# MasterOpAmp-design.net
KiCad netlist of a schematic drawn in EAGLE
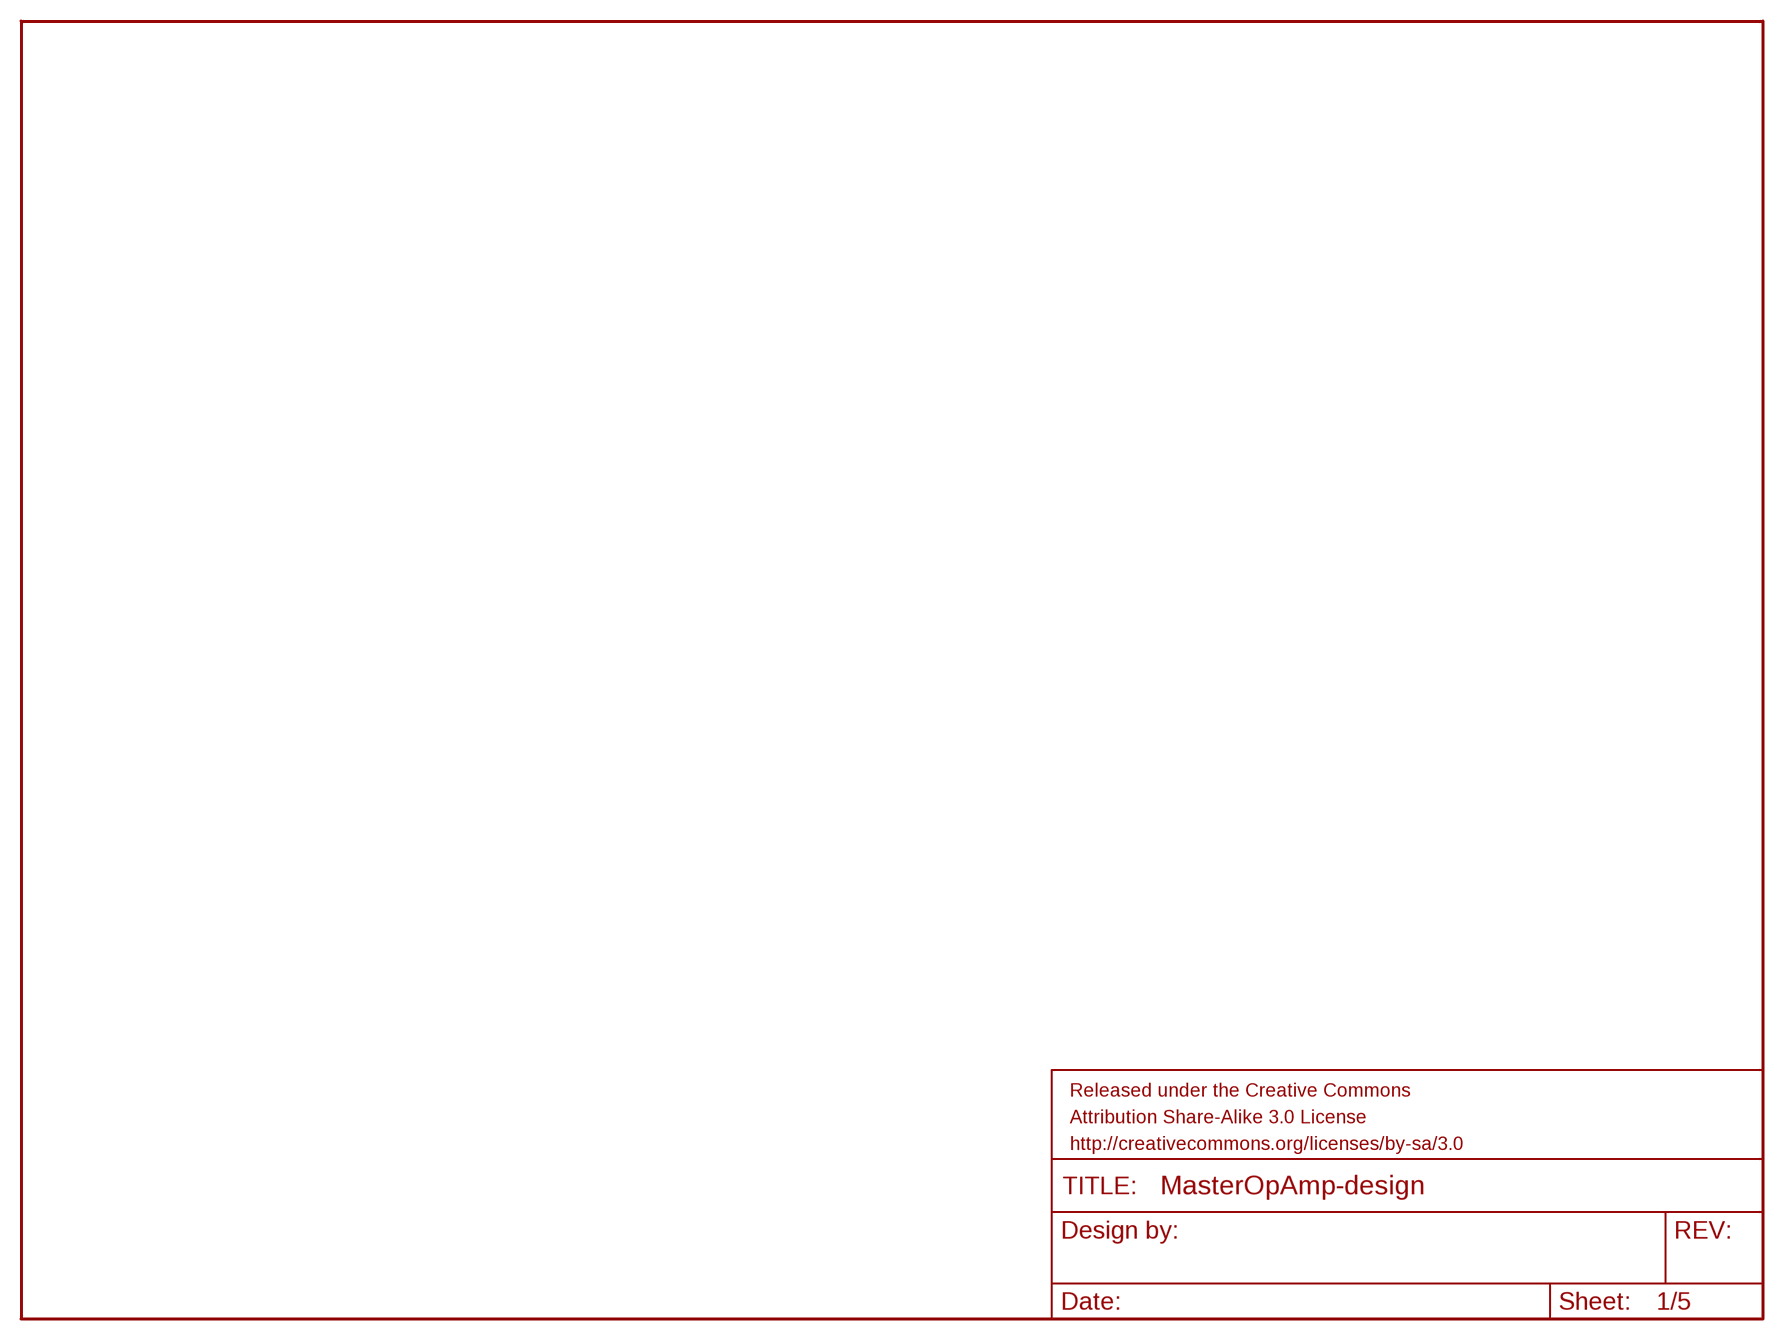
[diagram p0: schematic, sheet 1]
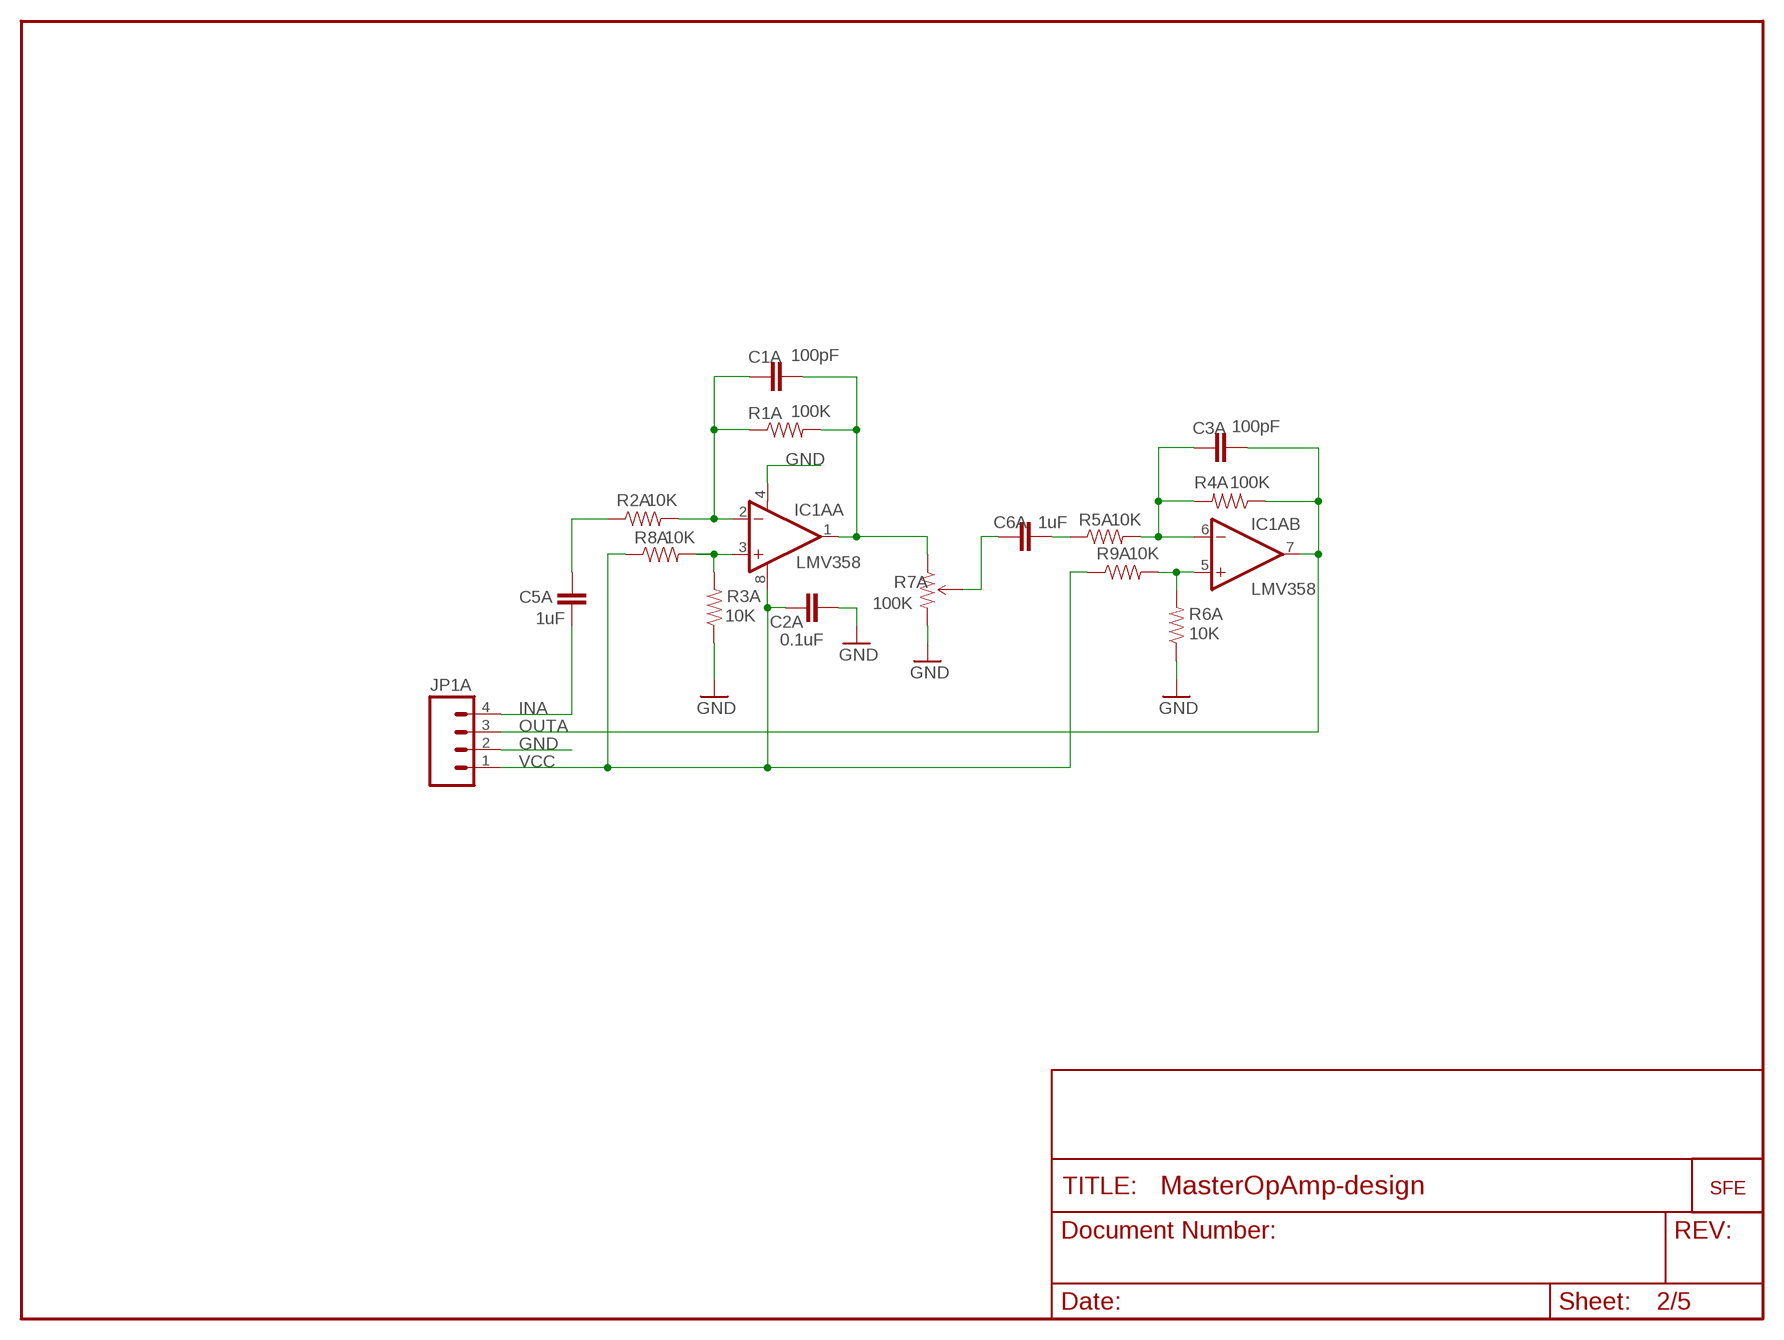
[diagram p1: schematic, sheet 2]
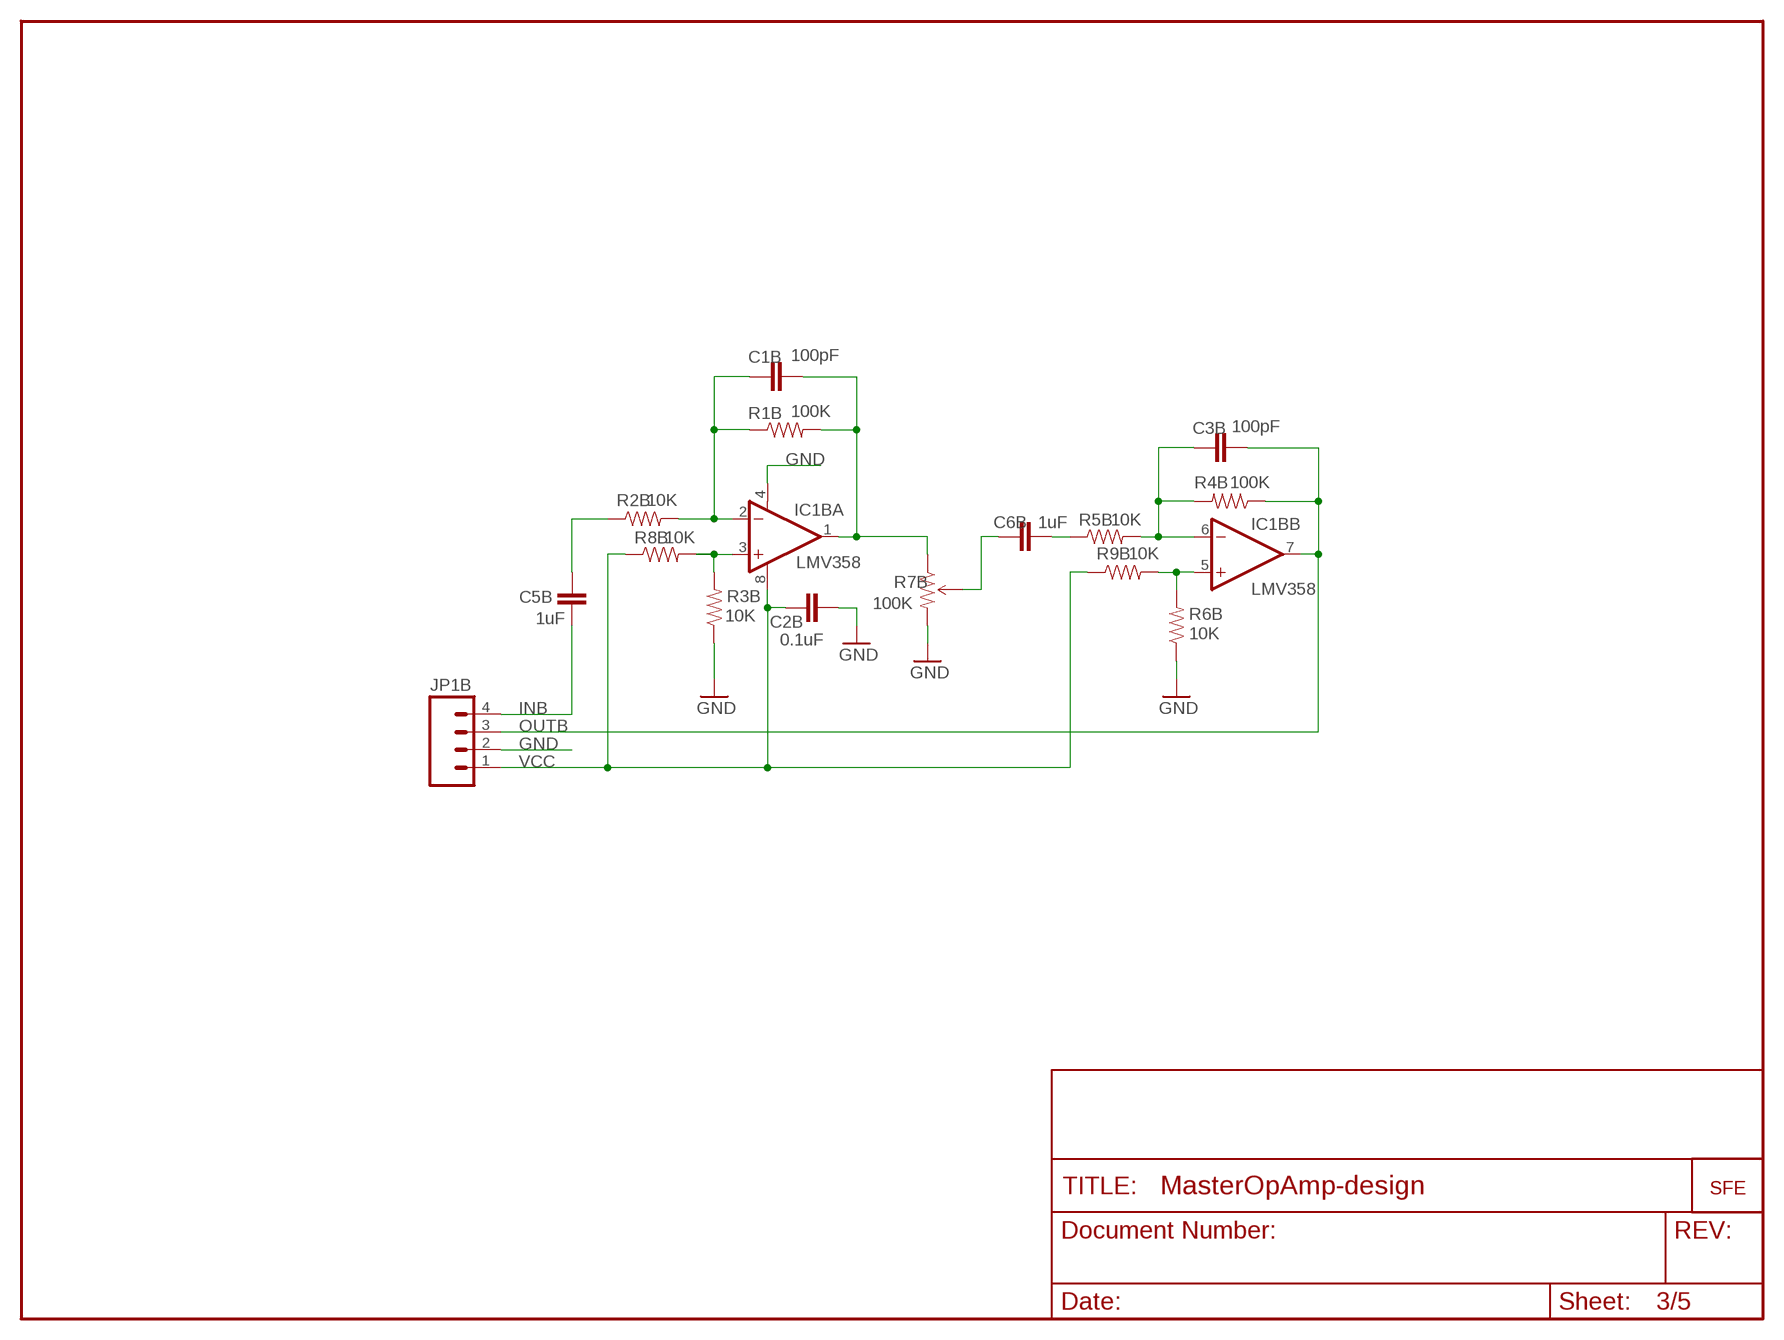
[diagram p2: schematic, sheet 3]
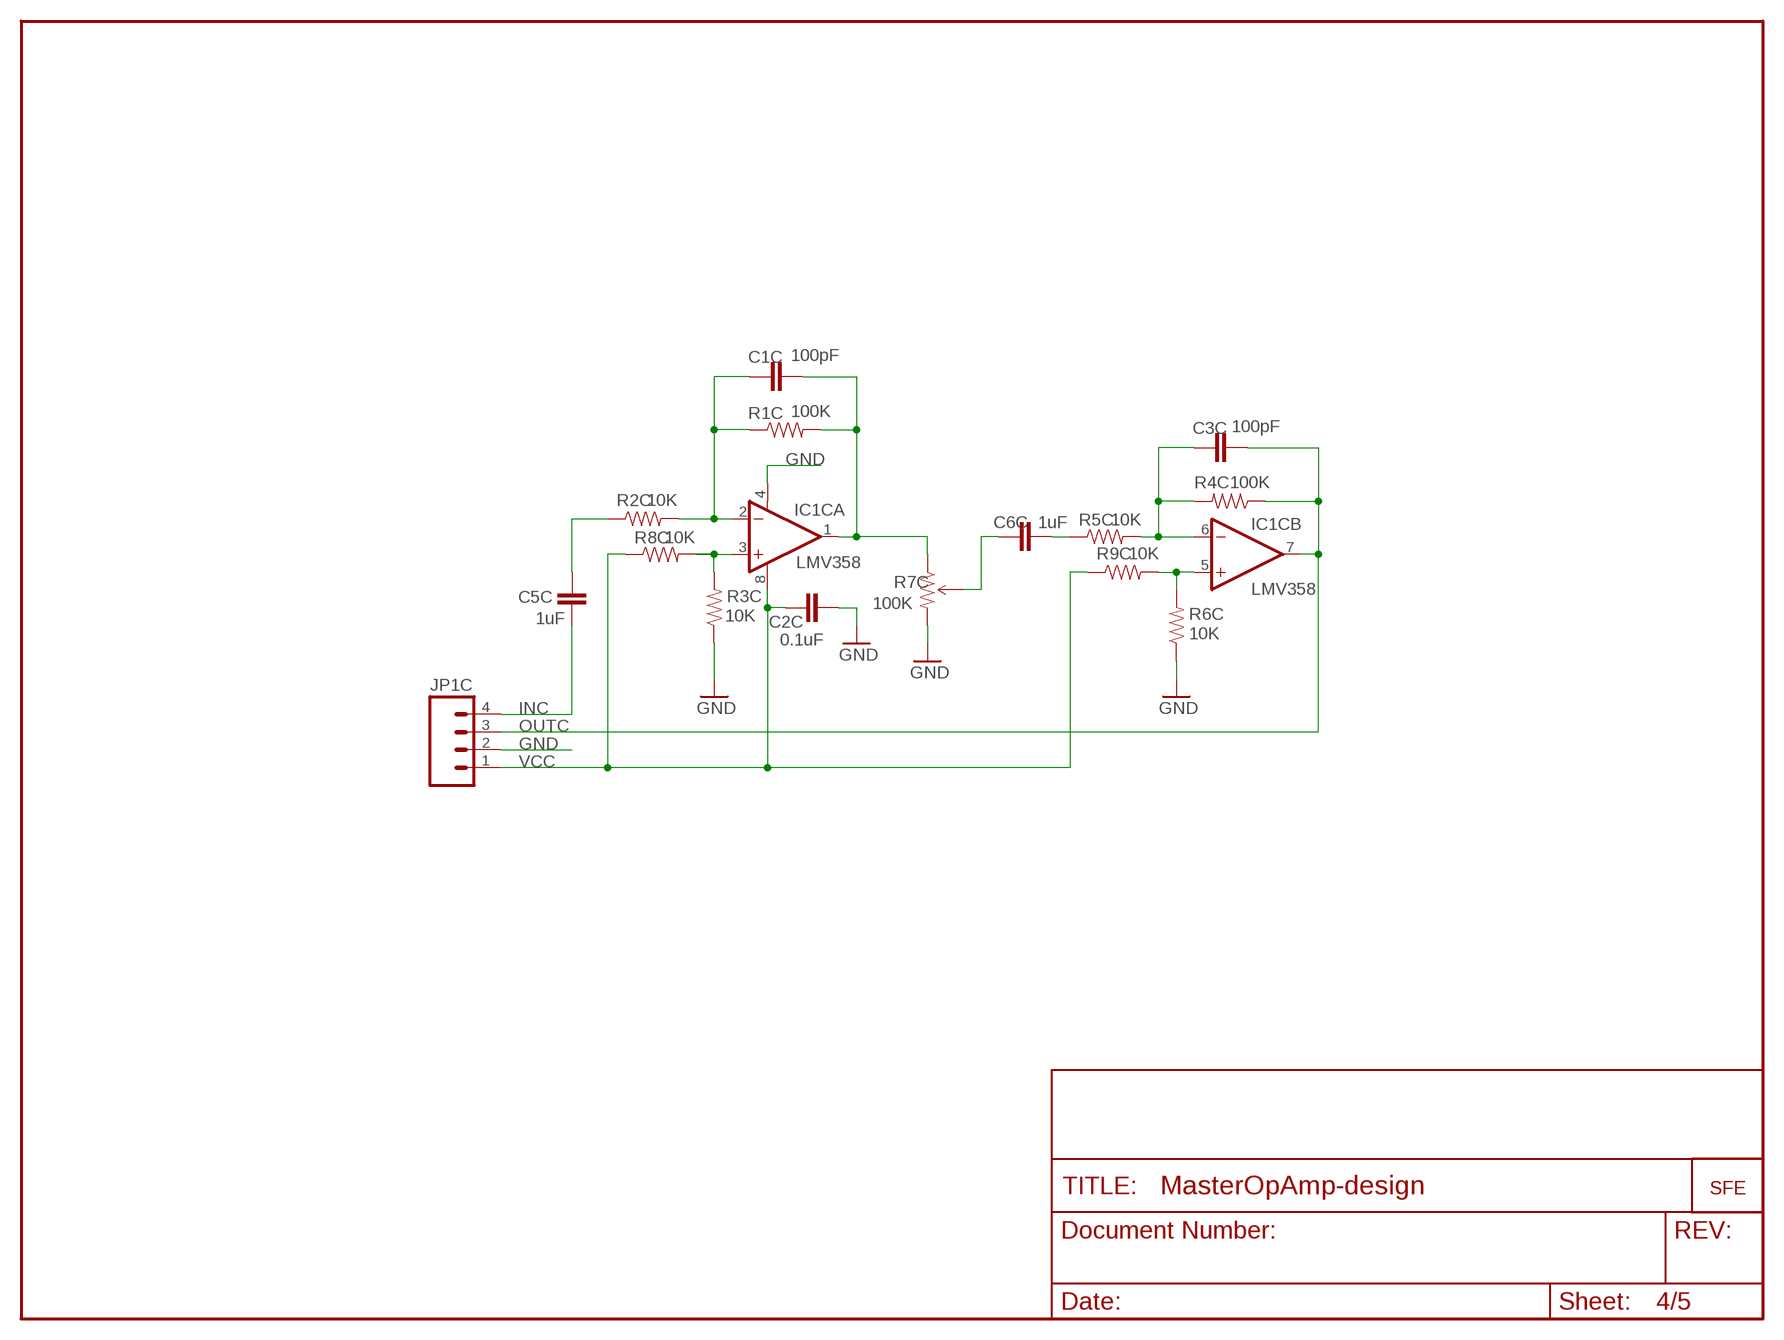
[diagram p3: schematic, sheet 4]
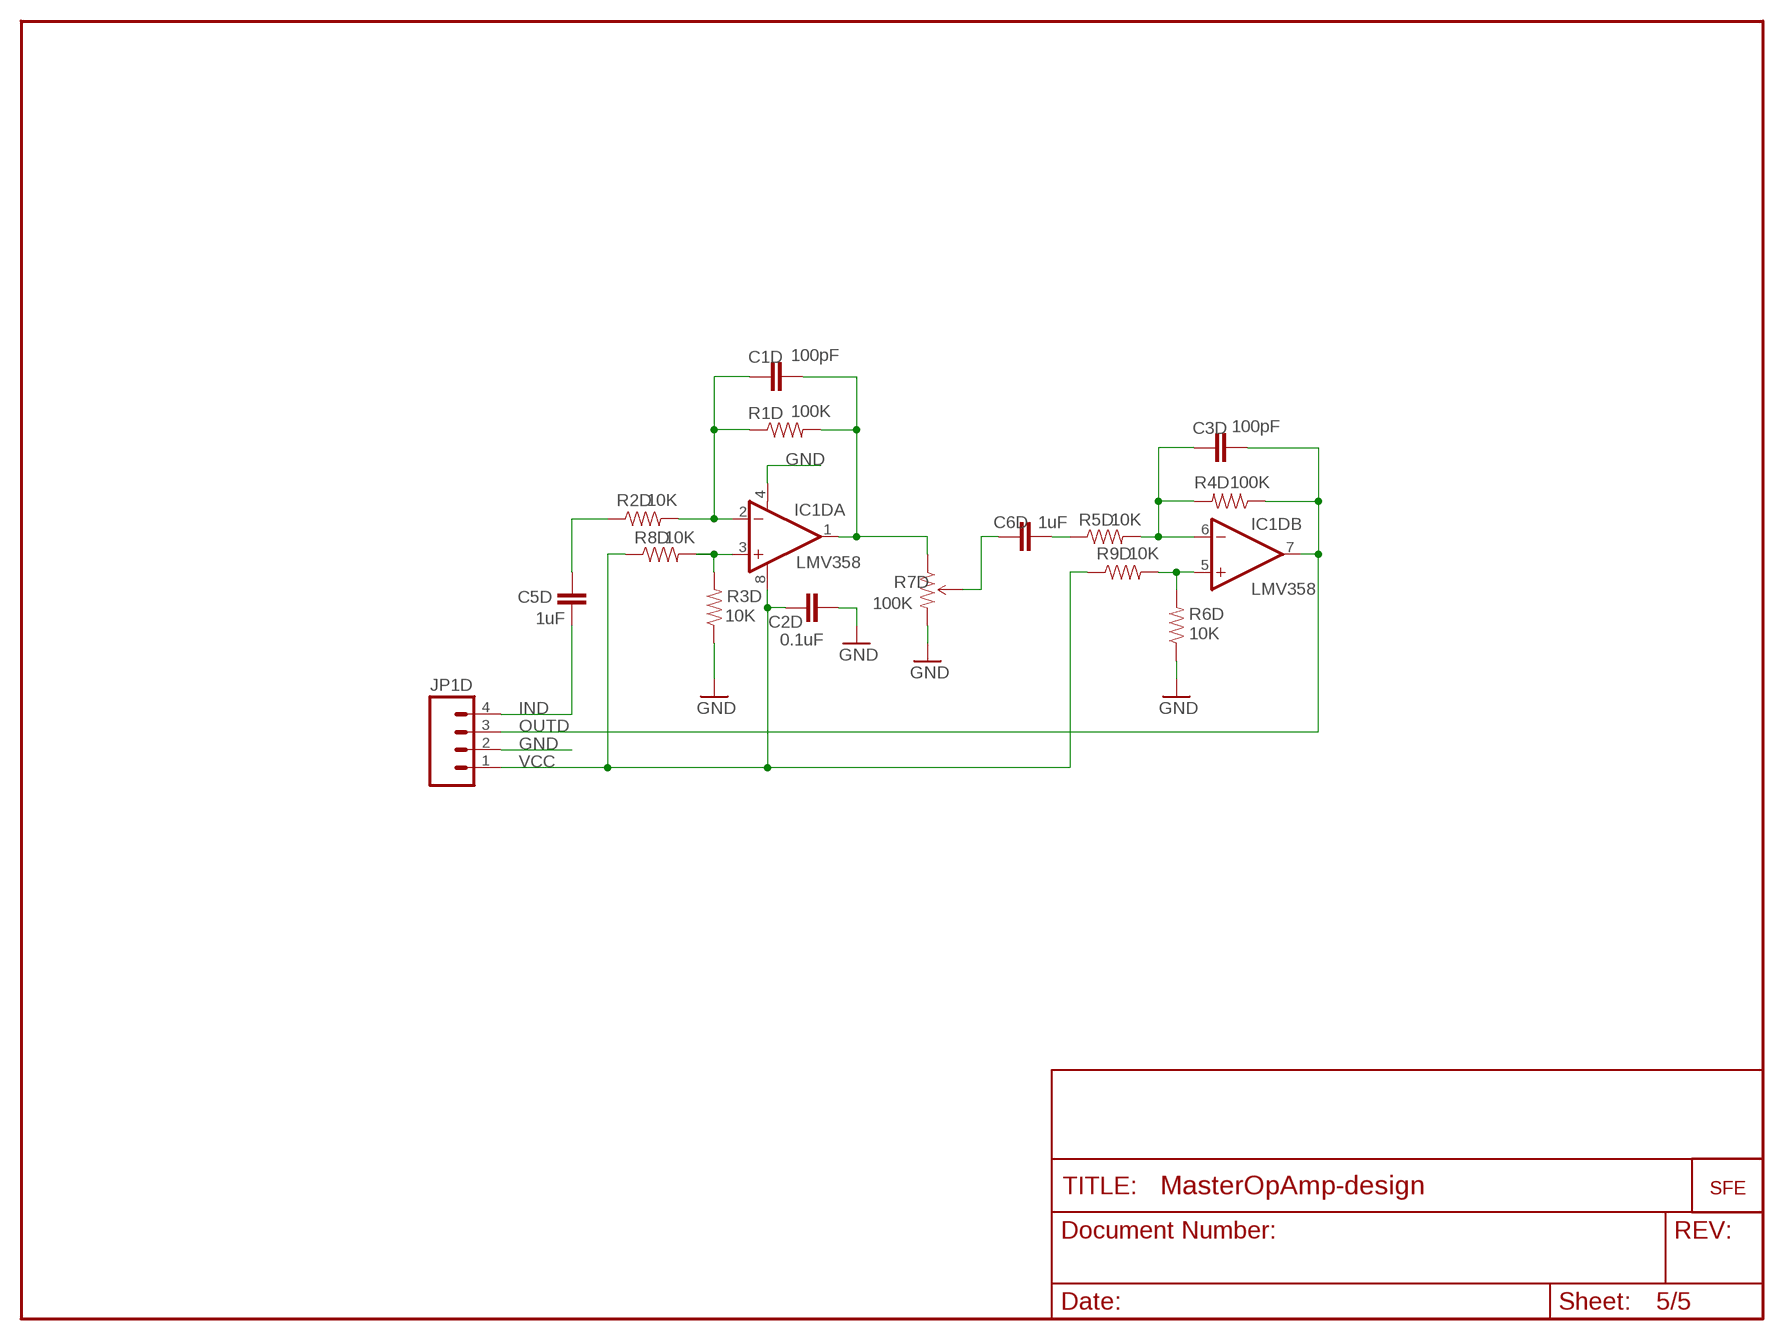
[diagram p4: schematic, sheet 5]

(export (version "E")
  (design (tool "Eeschema 10.0.6"))
  (components
    (comp (ref "C1A")
      (value "100pF")
      (footprint "eagle-import:C0402")
      (libsource (lib "eagle-import") (part "CAP0402"))
    )
    (comp (ref "C2A")
      (value "0.1uF")
      (footprint "eagle-import:C0402")
      (libsource (lib "eagle-import") (part "CAP0402"))
    )
    (comp (ref "C3A")
      (value "100pF")
      (footprint "eagle-import:C0402")
      (libsource (lib "eagle-import") (part "CAP0402"))
    )
    (comp (ref "C5A")
      (value "1uF")
      (footprint "eagle-import:C0402")
      (libsource (lib "eagle-import") (part "CAP0402"))
    )
    (comp (ref "C6A")
      (value "1uF")
      (footprint "eagle-import:C0402")
      (libsource (lib "eagle-import") (part "CAP0402"))
    )
    (comp (ref "IC1A")
      (value "LMV358")
      (footprint "eagle-import:SO08")
      (libsource (lib "eagle-import") (part "OPAMP-DUALU"))
    )
    (comp (ref "JP1A")
      (value "M04PTH")
      (footprint "eagle-import:1X04")
      (libsource (lib "eagle-import") (part "M04PTH"))
    )
    (comp (ref "R1A")
      (value "100K")
      (footprint "eagle-import:C0402")
      (libsource (lib "eagle-import") (part "RESISTOR0402"))
    )
    (comp (ref "R2A")
      (value "10K")
      (footprint "eagle-import:C0402")
      (libsource (lib "eagle-import") (part "RESISTOR0402"))
    )
    (comp (ref "R3A")
      (value "10K")
      (footprint "eagle-import:C0402")
      (libsource (lib "eagle-import") (part "RESISTOR0402"))
    )
    (comp (ref "R4A")
      (value "100K")
      (footprint "eagle-import:C0402")
      (libsource (lib "eagle-import") (part "RESISTOR0402"))
    )
    (comp (ref "R5A")
      (value "10K")
      (footprint "eagle-import:C0402")
      (libsource (lib "eagle-import") (part "RESISTOR0402"))
    )
    (comp (ref "R6A")
      (value "10K")
      (footprint "eagle-import:C0402")
      (libsource (lib "eagle-import") (part "RESISTOR0402"))
    )
    (comp (ref "R7A")
      (value "100K")
      (footprint "eagle-import:TRIMPOT-3MM")
      (libsource (lib "eagle-import") (part "TRIMPOTSMD"))
    )
    (comp (ref "R8A")
      (value "10K")
      (footprint "eagle-import:C0402")
      (libsource (lib "eagle-import") (part "SparkFun-DC_RESISTOR0402"))
    )
    (comp (ref "R9A")
      (value "10K")
      (footprint "eagle-import:C0402")
      (libsource (lib "eagle-import") (part "SparkFun-DC_RESISTOR0402"))
    )
    (comp (ref "U$3A")
      (value "LOGO-SFENEW")
      (footprint "eagle-import:SFE-NEW-WEBLOGO")
      (libsource (lib "eagle-import") (part "LOGO-SFENEW"))
    )
    (comp (ref "FRAME1")
      (value "FRAME-LETTER")
      (footprint "eagle-import:CREATIVE_COMMONS")
      (libsource (lib "eagle-import") (part "SparkFun-Aesthetics_FRAME-LETTER"))
    )
    (comp (ref "C1B")
      (value "100pF")
      (footprint "eagle-import:C0402")
      (libsource (lib "eagle-import") (part "CAP0402"))
    )
    (comp (ref "C2B")
      (value "0.1uF")
      (footprint "eagle-import:C0402")
      (libsource (lib "eagle-import") (part "CAP0402"))
    )
    (comp (ref "C3B")
      (value "100pF")
      (footprint "eagle-import:C0402")
      (libsource (lib "eagle-import") (part "CAP0402"))
    )
    (comp (ref "C5B")
      (value "1uF")
      (footprint "eagle-import:C0402")
      (libsource (lib "eagle-import") (part "CAP0402"))
    )
    (comp (ref "C6B")
      (value "1uF")
      (footprint "eagle-import:C0402")
      (libsource (lib "eagle-import") (part "CAP0402"))
    )
    (comp (ref "IC1B")
      (value "LMV358")
      (footprint "eagle-import:SO08")
      (libsource (lib "eagle-import") (part "OPAMP-DUALU"))
    )
    (comp (ref "JP1B")
      (value "M04PTH")
      (footprint "eagle-import:1X04")
      (libsource (lib "eagle-import") (part "M04PTH"))
    )
    (comp (ref "R1B")
      (value "100K")
      (footprint "eagle-import:C0402")
      (libsource (lib "eagle-import") (part "RESISTOR0402"))
    )
    (comp (ref "R2B")
      (value "10K")
      (footprint "eagle-import:C0402")
      (libsource (lib "eagle-import") (part "RESISTOR0402"))
    )
    (comp (ref "R3B")
      (value "10K")
      (footprint "eagle-import:C0402")
      (libsource (lib "eagle-import") (part "RESISTOR0402"))
    )
    (comp (ref "R4B")
      (value "100K")
      (footprint "eagle-import:C0402")
      (libsource (lib "eagle-import") (part "RESISTOR0402"))
    )
    (comp (ref "R5B")
      (value "10K")
      (footprint "eagle-import:C0402")
      (libsource (lib "eagle-import") (part "RESISTOR0402"))
    )
    (comp (ref "R6B")
      (value "10K")
      (footprint "eagle-import:C0402")
      (libsource (lib "eagle-import") (part "RESISTOR0402"))
    )
    (comp (ref "R7B")
      (value "100K")
      (footprint "eagle-import:TRIMPOT-3MM")
      (libsource (lib "eagle-import") (part "TRIMPOTSMD"))
    )
    (comp (ref "R8B")
      (value "10K")
      (footprint "eagle-import:C0402")
      (libsource (lib "eagle-import") (part "SparkFun-DC_RESISTOR0402"))
    )
    (comp (ref "R9B")
      (value "10K")
      (footprint "eagle-import:C0402")
      (libsource (lib "eagle-import") (part "SparkFun-DC_RESISTOR0402"))
    )
    (comp (ref "U$3B")
      (value "LOGO-SFENEW")
      (footprint "eagle-import:SFE-NEW-WEBLOGO")
      (libsource (lib "eagle-import") (part "LOGO-SFENEW"))
    )
    (comp (ref "C1C")
      (value "100pF")
      (footprint "eagle-import:C0402")
      (libsource (lib "eagle-import") (part "CAP0402"))
    )
    (comp (ref "C2C")
      (value "0.1uF")
      (footprint "eagle-import:C0402")
      (libsource (lib "eagle-import") (part "CAP0402"))
    )
    (comp (ref "C3C")
      (value "100pF")
      (footprint "eagle-import:C0402")
      (libsource (lib "eagle-import") (part "CAP0402"))
    )
    (comp (ref "C5C")
      (value "1uF")
      (footprint "eagle-import:C0402")
      (libsource (lib "eagle-import") (part "CAP0402"))
    )
    (comp (ref "C6C")
      (value "1uF")
      (footprint "eagle-import:C0402")
      (libsource (lib "eagle-import") (part "CAP0402"))
    )
    (comp (ref "IC1C")
      (value "LMV358")
      (footprint "eagle-import:SO08")
      (libsource (lib "eagle-import") (part "OPAMP-DUALU"))
    )
    (comp (ref "JP1C")
      (value "M04PTH")
      (footprint "eagle-import:1X04")
      (libsource (lib "eagle-import") (part "M04PTH"))
    )
    (comp (ref "R1C")
      (value "100K")
      (footprint "eagle-import:C0402")
      (libsource (lib "eagle-import") (part "RESISTOR0402"))
    )
    (comp (ref "R2C")
      (value "10K")
      (footprint "eagle-import:C0402")
      (libsource (lib "eagle-import") (part "RESISTOR0402"))
    )
    (comp (ref "R3C")
      (value "10K")
      (footprint "eagle-import:C0402")
      (libsource (lib "eagle-import") (part "RESISTOR0402"))
    )
    (comp (ref "R4C")
      (value "100K")
      (footprint "eagle-import:C0402")
      (libsource (lib "eagle-import") (part "RESISTOR0402"))
    )
    (comp (ref "R5C")
      (value "10K")
      (footprint "eagle-import:C0402")
      (libsource (lib "eagle-import") (part "RESISTOR0402"))
    )
    (comp (ref "R6C")
      (value "10K")
      (footprint "eagle-import:C0402")
      (libsource (lib "eagle-import") (part "RESISTOR0402"))
    )
    (comp (ref "R7C")
      (value "100K")
      (footprint "eagle-import:TRIMPOT-3MM")
      (libsource (lib "eagle-import") (part "TRIMPOTSMD"))
    )
    (comp (ref "R8C")
      (value "10K")
      (footprint "eagle-import:C0402")
      (libsource (lib "eagle-import") (part "SparkFun-DC_RESISTOR0402"))
    )
    (comp (ref "R9C")
      (value "10K")
      (footprint "eagle-import:C0402")
      (libsource (lib "eagle-import") (part "SparkFun-DC_RESISTOR0402"))
    )
    (comp (ref "U$3C")
      (value "LOGO-SFENEW")
      (footprint "eagle-import:SFE-NEW-WEBLOGO")
      (libsource (lib "eagle-import") (part "LOGO-SFENEW"))
    )
    (comp (ref "C1D")
      (value "100pF")
      (footprint "eagle-import:C0402")
      (libsource (lib "eagle-import") (part "CAP0402"))
    )
    (comp (ref "C2D")
      (value "0.1uF")
      (footprint "eagle-import:C0402")
      (libsource (lib "eagle-import") (part "CAP0402"))
    )
    (comp (ref "C3D")
      (value "100pF")
      (footprint "eagle-import:C0402")
      (libsource (lib "eagle-import") (part "CAP0402"))
    )
    (comp (ref "C5D")
      (value "1uF")
      (footprint "eagle-import:C0402")
      (libsource (lib "eagle-import") (part "CAP0402"))
    )
    (comp (ref "C6D")
      (value "1uF")
      (footprint "eagle-import:C0402")
      (libsource (lib "eagle-import") (part "CAP0402"))
    )
    (comp (ref "IC1D")
      (value "LMV358")
      (footprint "eagle-import:SO08")
      (libsource (lib "eagle-import") (part "OPAMP-DUALU"))
    )
    (comp (ref "JP1D")
      (value "M04PTH")
      (footprint "eagle-import:1X04")
      (libsource (lib "eagle-import") (part "M04PTH"))
    )
    (comp (ref "R1D")
      (value "100K")
      (footprint "eagle-import:C0402")
      (libsource (lib "eagle-import") (part "RESISTOR0402"))
    )
    (comp (ref "R2D")
      (value "10K")
      (footprint "eagle-import:C0402")
      (libsource (lib "eagle-import") (part "RESISTOR0402"))
    )
    (comp (ref "R3D")
      (value "10K")
      (footprint "eagle-import:C0402")
      (libsource (lib "eagle-import") (part "RESISTOR0402"))
    )
    (comp (ref "R4D")
      (value "100K")
      (footprint "eagle-import:C0402")
      (libsource (lib "eagle-import") (part "RESISTOR0402"))
    )
    (comp (ref "R5D")
      (value "10K")
      (footprint "eagle-import:C0402")
      (libsource (lib "eagle-import") (part "RESISTOR0402"))
    )
    (comp (ref "R6D")
      (value "10K")
      (footprint "eagle-import:C0402")
      (libsource (lib "eagle-import") (part "RESISTOR0402"))
    )
    (comp (ref "R7D")
      (value "100K")
      (footprint "eagle-import:TRIMPOT-3MM")
      (libsource (lib "eagle-import") (part "TRIMPOTSMD"))
    )
    (comp (ref "R8D")
      (value "10K")
      (footprint "eagle-import:C0402")
      (libsource (lib "eagle-import") (part "SparkFun-DC_RESISTOR0402"))
    )
    (comp (ref "R9D")
      (value "10K")
      (footprint "eagle-import:C0402")
      (libsource (lib "eagle-import") (part "SparkFun-DC_RESISTOR0402"))
    )
    (comp (ref "U$3D")
      (value "LOGO-SFENEW")
      (footprint "eagle-import:SFE-NEW-WEBLOGO")
      (libsource (lib "eagle-import") (part "LOGO-SFENEW"))
    )
  )
  (nets
    (net (code "1") (name "GND") (class "Default")
      (node (ref "C2A") (pin "2") (pinfunction "2_2") (pintype "passive"))
      (node (ref "C2B") (pin "2") (pinfunction "2_2") (pintype "passive"))
      (node (ref "C2C") (pin "2") (pinfunction "2_2") (pintype "passive"))
      (node (ref "C2D") (pin "2") (pinfunction "2_2") (pintype "passive"))
      (node (ref "IC1A") (pin "4") (pinfunction "V-_4") (pintype "power_in"))
      (node (ref "IC1B") (pin "4") (pinfunction "V-_4") (pintype "power_in"))
      (node (ref "IC1C") (pin "4") (pinfunction "V-_4") (pintype "power_in"))
      (node (ref "IC1D") (pin "4") (pinfunction "V-_4") (pintype "power_in"))
      (node (ref "JP1A") (pin "2") (pinfunction "2_2") (pintype "passive"))
      (node (ref "JP1B") (pin "2") (pinfunction "2_2") (pintype "passive"))
      (node (ref "JP1C") (pin "2") (pinfunction "2_2") (pintype "passive"))
      (node (ref "JP1D") (pin "2") (pinfunction "2_2") (pintype "passive"))
      (node (ref "R3A") (pin "1") (pinfunction "1_1") (pintype "passive"))
      (node (ref "R3B") (pin "1") (pinfunction "1_1") (pintype "passive"))
      (node (ref "R3C") (pin "1") (pinfunction "1_1") (pintype "passive"))
      (node (ref "R3D") (pin "1") (pinfunction "1_1") (pintype "passive"))
      (node (ref "R6A") (pin "1") (pinfunction "1_1") (pintype "passive"))
      (node (ref "R6B") (pin "1") (pinfunction "1_1") (pintype "passive"))
      (node (ref "R6C") (pin "1") (pinfunction "1_1") (pintype "passive"))
      (node (ref "R6D") (pin "1") (pinfunction "1_1") (pintype "passive"))
      (node (ref "R7A") (pin "3") (pinfunction "CW_3") (pintype "passive"))
      (node (ref "R7B") (pin "3") (pinfunction "CW_3") (pintype "passive"))
      (node (ref "R7C") (pin "3") (pinfunction "CW_3") (pintype "passive"))
      (node (ref "R7D") (pin "3") (pinfunction "CW_3") (pintype "passive"))
    )
    (net (code "2") (name "INA") (class "Default")
      (node (ref "C5A") (pin "1") (pinfunction "1_1") (pintype "passive"))
      (node (ref "JP1A") (pin "4") (pinfunction "4_4") (pintype "passive"))
    )
    (net (code "3") (name "INB") (class "Default")
      (node (ref "C5B") (pin "1") (pinfunction "1_1") (pintype "passive"))
      (node (ref "JP1B") (pin "4") (pinfunction "4_4") (pintype "passive"))
    )
    (net (code "4") (name "INC") (class "Default")
      (node (ref "C5C") (pin "1") (pinfunction "1_1") (pintype "passive"))
      (node (ref "JP1C") (pin "4") (pinfunction "4_4") (pintype "passive"))
    )
    (net (code "5") (name "IND") (class "Default")
      (node (ref "C5D") (pin "1") (pinfunction "1_1") (pintype "passive"))
      (node (ref "JP1D") (pin "4") (pinfunction "4_4") (pintype "passive"))
    )
    (net (code "6") (name "Net-(C5A-Pad2)") (class "Default")
      (node (ref "C5A") (pin "2") (pinfunction "2_2") (pintype "passive"))
      (node (ref "R2A") (pin "1") (pinfunction "1_1") (pintype "passive"))
    )
    (net (code "7") (name "Net-(C5B-Pad2)") (class "Default")
      (node (ref "C5B") (pin "2") (pinfunction "2_2") (pintype "passive"))
      (node (ref "R2B") (pin "1") (pinfunction "1_1") (pintype "passive"))
    )
    (net (code "8") (name "Net-(C5C-Pad2)") (class "Default")
      (node (ref "C5C") (pin "2") (pinfunction "2_2") (pintype "passive"))
      (node (ref "R2C") (pin "1") (pinfunction "1_1") (pintype "passive"))
    )
    (net (code "9") (name "Net-(C5D-Pad2)") (class "Default")
      (node (ref "C5D") (pin "2") (pinfunction "2_2") (pintype "passive"))
      (node (ref "R2D") (pin "1") (pinfunction "1_1") (pintype "passive"))
    )
    (net (code "10") (name "Net-(C6A-Pad1)") (class "Default")
      (node (ref "C6A") (pin "1") (pinfunction "1_1") (pintype "passive"))
      (node (ref "R5A") (pin "1") (pinfunction "1_1") (pintype "passive"))
    )
    (net (code "11") (name "Net-(C6B-Pad1)") (class "Default")
      (node (ref "C6B") (pin "1") (pinfunction "1_1") (pintype "passive"))
      (node (ref "R5B") (pin "1") (pinfunction "1_1") (pintype "passive"))
    )
    (net (code "12") (name "Net-(C6C-Pad1)") (class "Default")
      (node (ref "C6C") (pin "1") (pinfunction "1_1") (pintype "passive"))
      (node (ref "R5C") (pin "1") (pinfunction "1_1") (pintype "passive"))
    )
    (net (code "13") (name "Net-(C6D-Pad1)") (class "Default")
      (node (ref "C6D") (pin "1") (pinfunction "1_1") (pintype "passive"))
      (node (ref "R5D") (pin "1") (pinfunction "1_1") (pintype "passive"))
    )
    (net (code "14") (name "Net-(IC1AA-+IN)") (class "Default")
      (node (ref "IC1A") (pin "3") (pinfunction "+IN_3") (pintype "input"))
      (node (ref "R3A") (pin "2") (pinfunction "2_2") (pintype "passive"))
      (node (ref "R8A") (pin "2") (pinfunction "2_2") (pintype "passive"))
    )
    (net (code "15") (name "Net-(IC1AA--IN)") (class "Default")
      (node (ref "C1A") (pin "1") (pinfunction "1_1") (pintype "passive"))
      (node (ref "IC1A") (pin "2") (pinfunction "-IN_2") (pintype "input"))
      (node (ref "R1A") (pin "1") (pinfunction "1_1") (pintype "passive"))
      (node (ref "R2A") (pin "2") (pinfunction "2_2") (pintype "passive"))
    )
    (net (code "16") (name "Net-(IC1AA-OUT)") (class "Default")
      (node (ref "C1A") (pin "2") (pinfunction "2_2") (pintype "passive"))
      (node (ref "IC1A") (pin "1") (pinfunction "OUT_1") (pintype "output"))
      (node (ref "R1A") (pin "2") (pinfunction "2_2") (pintype "passive"))
      (node (ref "R7A") (pin "1") (pinfunction "CCW_1") (pintype "passive"))
    )
    (net (code "17") (name "Net-(IC1AB-+IN)") (class "Default")
      (node (ref "IC1A") (pin "5") (pinfunction "+IN_5") (pintype "input"))
      (node (ref "R6A") (pin "2") (pinfunction "2_2") (pintype "passive"))
      (node (ref "R9A") (pin "2") (pinfunction "2_2") (pintype "passive"))
    )
    (net (code "18") (name "Net-(IC1AB--IN)") (class "Default")
      (node (ref "C3A") (pin "1") (pinfunction "1_1") (pintype "passive"))
      (node (ref "IC1A") (pin "6") (pinfunction "-IN_6") (pintype "input"))
      (node (ref "R4A") (pin "2") (pinfunction "2_2") (pintype "passive"))
      (node (ref "R5A") (pin "2") (pinfunction "2_2") (pintype "passive"))
    )
    (net (code "19") (name "Net-(IC1BA-+IN)") (class "Default")
      (node (ref "IC1B") (pin "3") (pinfunction "+IN_3") (pintype "input"))
      (node (ref "R3B") (pin "2") (pinfunction "2_2") (pintype "passive"))
      (node (ref "R8B") (pin "2") (pinfunction "2_2") (pintype "passive"))
    )
    (net (code "20") (name "Net-(IC1BA--IN)") (class "Default")
      (node (ref "C1B") (pin "1") (pinfunction "1_1") (pintype "passive"))
      (node (ref "IC1B") (pin "2") (pinfunction "-IN_2") (pintype "input"))
      (node (ref "R1B") (pin "1") (pinfunction "1_1") (pintype "passive"))
      (node (ref "R2B") (pin "2") (pinfunction "2_2") (pintype "passive"))
    )
    (net (code "21") (name "Net-(IC1BA-OUT)") (class "Default")
      (node (ref "C1B") (pin "2") (pinfunction "2_2") (pintype "passive"))
      (node (ref "IC1B") (pin "1") (pinfunction "OUT_1") (pintype "output"))
      (node (ref "R1B") (pin "2") (pinfunction "2_2") (pintype "passive"))
      (node (ref "R7B") (pin "1") (pinfunction "CCW_1") (pintype "passive"))
    )
    (net (code "22") (name "Net-(IC1BB-+IN)") (class "Default")
      (node (ref "IC1B") (pin "5") (pinfunction "+IN_5") (pintype "input"))
      (node (ref "R6B") (pin "2") (pinfunction "2_2") (pintype "passive"))
      (node (ref "R9B") (pin "2") (pinfunction "2_2") (pintype "passive"))
    )
    (net (code "23") (name "Net-(IC1BB--IN)") (class "Default")
      (node (ref "C3B") (pin "1") (pinfunction "1_1") (pintype "passive"))
      (node (ref "IC1B") (pin "6") (pinfunction "-IN_6") (pintype "input"))
      (node (ref "R4B") (pin "2") (pinfunction "2_2") (pintype "passive"))
      (node (ref "R5B") (pin "2") (pinfunction "2_2") (pintype "passive"))
    )
    (net (code "24") (name "Net-(IC1CA-+IN)") (class "Default")
      (node (ref "IC1C") (pin "3") (pinfunction "+IN_3") (pintype "input"))
      (node (ref "R3C") (pin "2") (pinfunction "2_2") (pintype "passive"))
      (node (ref "R8C") (pin "2") (pinfunction "2_2") (pintype "passive"))
    )
    (net (code "25") (name "Net-(IC1CA--IN)") (class "Default")
      (node (ref "C1C") (pin "1") (pinfunction "1_1") (pintype "passive"))
      (node (ref "IC1C") (pin "2") (pinfunction "-IN_2") (pintype "input"))
      (node (ref "R1C") (pin "1") (pinfunction "1_1") (pintype "passive"))
      (node (ref "R2C") (pin "2") (pinfunction "2_2") (pintype "passive"))
    )
    (net (code "26") (name "Net-(IC1CA-OUT)") (class "Default")
      (node (ref "C1C") (pin "2") (pinfunction "2_2") (pintype "passive"))
      (node (ref "IC1C") (pin "1") (pinfunction "OUT_1") (pintype "output"))
      (node (ref "R1C") (pin "2") (pinfunction "2_2") (pintype "passive"))
      (node (ref "R7C") (pin "1") (pinfunction "CCW_1") (pintype "passive"))
    )
    (net (code "27") (name "Net-(IC1CB-+IN)") (class "Default")
      (node (ref "IC1C") (pin "5") (pinfunction "+IN_5") (pintype "input"))
      (node (ref "R6C") (pin "2") (pinfunction "2_2") (pintype "passive"))
      (node (ref "R9C") (pin "2") (pinfunction "2_2") (pintype "passive"))
    )
    (net (code "28") (name "Net-(IC1CB--IN)") (class "Default")
      (node (ref "C3C") (pin "1") (pinfunction "1_1") (pintype "passive"))
      (node (ref "IC1C") (pin "6") (pinfunction "-IN_6") (pintype "input"))
      (node (ref "R4C") (pin "2") (pinfunction "2_2") (pintype "passive"))
      (node (ref "R5C") (pin "2") (pinfunction "2_2") (pintype "passive"))
    )
    (net (code "29") (name "Net-(IC1DA-+IN)") (class "Default")
      (node (ref "IC1D") (pin "3") (pinfunction "+IN_3") (pintype "input"))
      (node (ref "R3D") (pin "2") (pinfunction "2_2") (pintype "passive"))
      (node (ref "R8D") (pin "2") (pinfunction "2_2") (pintype "passive"))
    )
    (net (code "30") (name "Net-(IC1DA--IN)") (class "Default")
      (node (ref "C1D") (pin "1") (pinfunction "1_1") (pintype "passive"))
      (node (ref "IC1D") (pin "2") (pinfunction "-IN_2") (pintype "input"))
      (node (ref "R1D") (pin "1") (pinfunction "1_1") (pintype "passive"))
      (node (ref "R2D") (pin "2") (pinfunction "2_2") (pintype "passive"))
    )
    (net (code "31") (name "Net-(IC1DA-OUT)") (class "Default")
      (node (ref "C1D") (pin "2") (pinfunction "2_2") (pintype "passive"))
      (node (ref "IC1D") (pin "1") (pinfunction "OUT_1") (pintype "output"))
      (node (ref "R1D") (pin "2") (pinfunction "2_2") (pintype "passive"))
      (node (ref "R7D") (pin "1") (pinfunction "CCW_1") (pintype "passive"))
    )
    (net (code "32") (name "Net-(IC1DB-+IN)") (class "Default")
      (node (ref "IC1D") (pin "5") (pinfunction "+IN_5") (pintype "input"))
      (node (ref "R6D") (pin "2") (pinfunction "2_2") (pintype "passive"))
      (node (ref "R9D") (pin "2") (pinfunction "2_2") (pintype "passive"))
    )
    (net (code "33") (name "Net-(IC1DB--IN)") (class "Default")
      (node (ref "C3D") (pin "1") (pinfunction "1_1") (pintype "passive"))
      (node (ref "IC1D") (pin "6") (pinfunction "-IN_6") (pintype "input"))
      (node (ref "R4D") (pin "2") (pinfunction "2_2") (pintype "passive"))
      (node (ref "R5D") (pin "2") (pinfunction "2_2") (pintype "passive"))
    )
    (net (code "34") (name "Net-(R7A-WIPER)") (class "Default")
      (node (ref "C6A") (pin "2") (pinfunction "2_2") (pintype "passive"))
      (node (ref "R7A") (pin "2") (pinfunction "WIPER_2") (pintype "passive"))
    )
    (net (code "35") (name "Net-(R7B-WIPER)") (class "Default")
      (node (ref "C6B") (pin "2") (pinfunction "2_2") (pintype "passive"))
      (node (ref "R7B") (pin "2") (pinfunction "WIPER_2") (pintype "passive"))
    )
    (net (code "36") (name "Net-(R7C-WIPER)") (class "Default")
      (node (ref "C6C") (pin "2") (pinfunction "2_2") (pintype "passive"))
      (node (ref "R7C") (pin "2") (pinfunction "WIPER_2") (pintype "passive"))
    )
    (net (code "37") (name "Net-(R7D-WIPER)") (class "Default")
      (node (ref "C6D") (pin "2") (pinfunction "2_2") (pintype "passive"))
      (node (ref "R7D") (pin "2") (pinfunction "WIPER_2") (pintype "passive"))
    )
    (net (code "38") (name "OUTA") (class "Default")
      (node (ref "C3A") (pin "2") (pinfunction "2_2") (pintype "passive"))
      (node (ref "IC1A") (pin "7") (pinfunction "OUT_7") (pintype "output"))
      (node (ref "JP1A") (pin "3") (pinfunction "3_3") (pintype "passive"))
      (node (ref "R4A") (pin "1") (pinfunction "1_1") (pintype "passive"))
    )
    (net (code "39") (name "OUTB") (class "Default")
      (node (ref "C3B") (pin "2") (pinfunction "2_2") (pintype "passive"))
      (node (ref "IC1B") (pin "7") (pinfunction "OUT_7") (pintype "output"))
      (node (ref "JP1B") (pin "3") (pinfunction "3_3") (pintype "passive"))
      (node (ref "R4B") (pin "1") (pinfunction "1_1") (pintype "passive"))
    )
    (net (code "40") (name "OUTC") (class "Default")
      (node (ref "C3C") (pin "2") (pinfunction "2_2") (pintype "passive"))
      (node (ref "IC1C") (pin "7") (pinfunction "OUT_7") (pintype "output"))
      (node (ref "JP1C") (pin "3") (pinfunction "3_3") (pintype "passive"))
      (node (ref "R4C") (pin "1") (pinfunction "1_1") (pintype "passive"))
    )
    (net (code "41") (name "OUTD") (class "Default")
      (node (ref "C3D") (pin "2") (pinfunction "2_2") (pintype "passive"))
      (node (ref "IC1D") (pin "7") (pinfunction "OUT_7") (pintype "output"))
      (node (ref "JP1D") (pin "3") (pinfunction "3_3") (pintype "passive"))
      (node (ref "R4D") (pin "1") (pinfunction "1_1") (pintype "passive"))
    )
    (net (code "42") (name "VCC") (class "Default")
      (node (ref "C2A") (pin "1") (pinfunction "1_1") (pintype "passive"))
      (node (ref "C2B") (pin "1") (pinfunction "1_1") (pintype "passive"))
      (node (ref "C2C") (pin "1") (pinfunction "1_1") (pintype "passive"))
      (node (ref "C2D") (pin "1") (pinfunction "1_1") (pintype "passive"))
      (node (ref "IC1A") (pin "8") (pinfunction "V+_8") (pintype "power_in"))
      (node (ref "IC1B") (pin "8") (pinfunction "V+_8") (pintype "power_in"))
      (node (ref "IC1C") (pin "8") (pinfunction "V+_8") (pintype "power_in"))
      (node (ref "IC1D") (pin "8") (pinfunction "V+_8") (pintype "power_in"))
      (node (ref "JP1A") (pin "1") (pinfunction "1_1") (pintype "passive"))
      (node (ref "JP1B") (pin "1") (pinfunction "1_1") (pintype "passive"))
      (node (ref "JP1C") (pin "1") (pinfunction "1_1") (pintype "passive"))
      (node (ref "JP1D") (pin "1") (pinfunction "1_1") (pintype "passive"))
      (node (ref "R8A") (pin "1") (pinfunction "1_1") (pintype "passive"))
      (node (ref "R8B") (pin "1") (pinfunction "1_1") (pintype "passive"))
      (node (ref "R8C") (pin "1") (pinfunction "1_1") (pintype "passive"))
      (node (ref "R8D") (pin "1") (pinfunction "1_1") (pintype "passive"))
      (node (ref "R9A") (pin "1") (pinfunction "1_1") (pintype "passive"))
      (node (ref "R9B") (pin "1") (pinfunction "1_1") (pintype "passive"))
      (node (ref "R9C") (pin "1") (pinfunction "1_1") (pintype "passive"))
      (node (ref "R9D") (pin "1") (pinfunction "1_1") (pintype "passive"))
    )
  )
)
